# Peripherals_2.net
KiCad netlist of a schematic drawn in Altium Designer
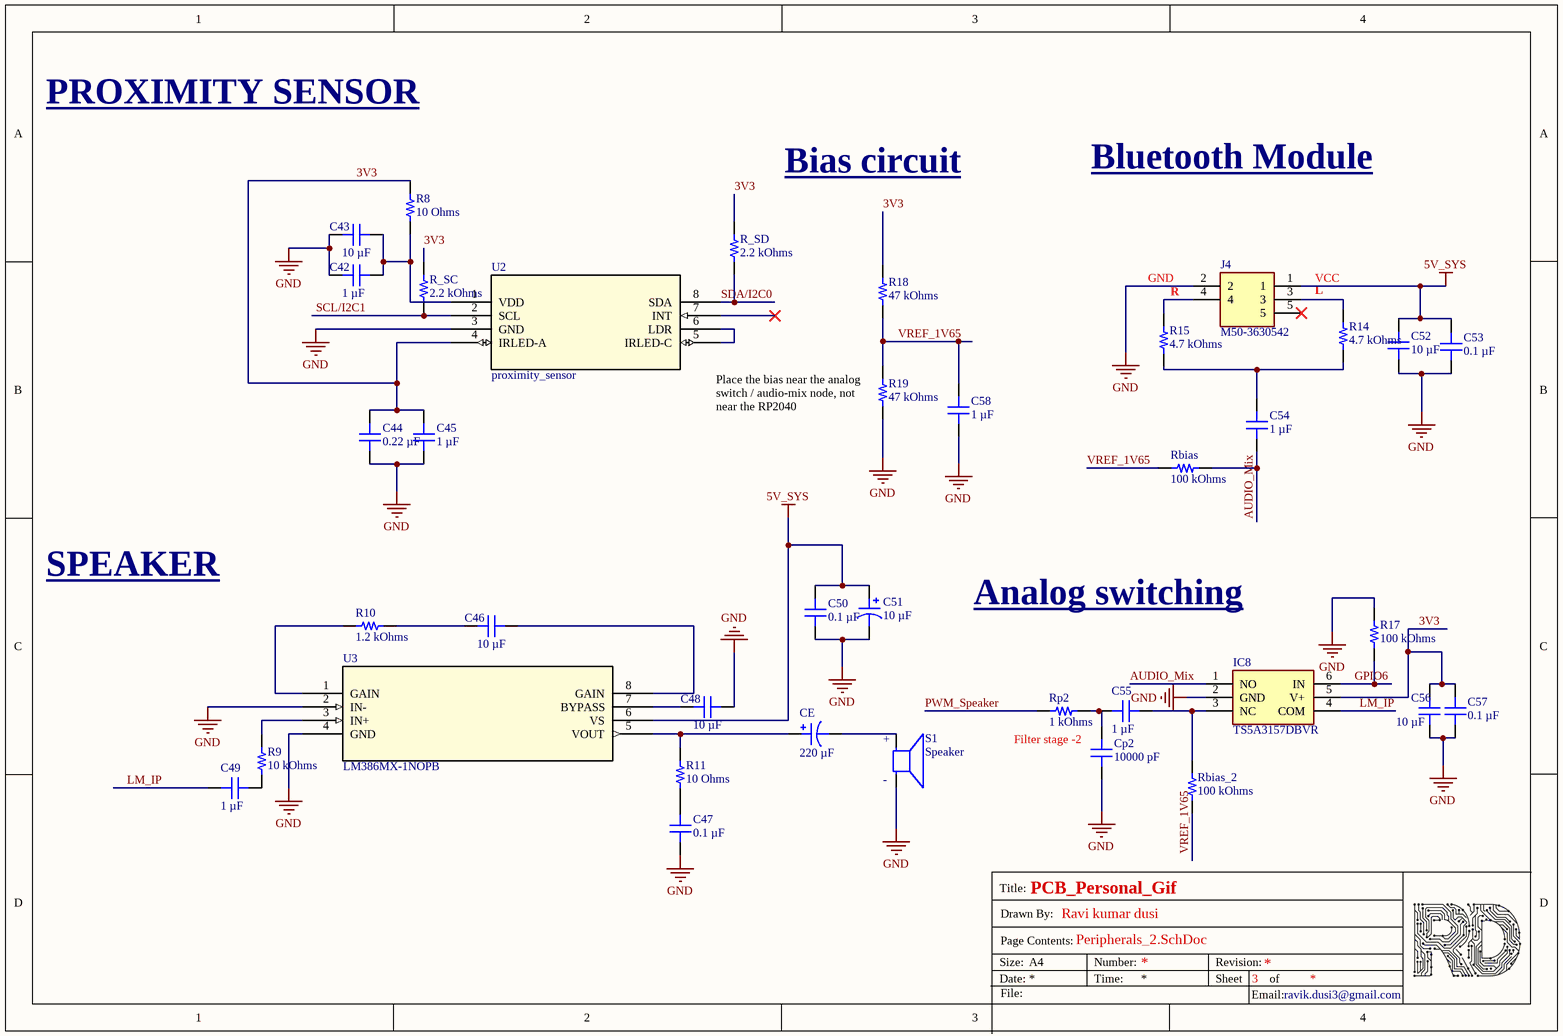
[diagram p0: Peripherals_2.SchDoc]

(export (version "E")
  (design (tool "Eeschema 10.0.6"))
  (components
    (comp (ref "C42")
      (value "1 µF")
      (footprint "CAP 0402_1005")
      (description "CAP CER 1UF 10V X7S 0402")
      (fields
        (field (name "PART NUMBER") "GRM155C71A105KE11D")
        (field (name "MANUFACTURER") "Murata Electronics")
      )
      (libsource (lib "Celestial Altium Library - altium_library") (part "Capacitor"))
    )
    (comp (ref "C43")
      (value "10 µF")
      (footprint "CAP 0402_1005")
      (description "CAP CER 10UF 10V X5R 0402")
      (fields
        (field (name "PART NUMBER") "CL05A106MP8NUB8")
        (field (name "MANUFACTURER") "Samsung Electro-Mechanics")
      )
      (libsource (lib "Celestial Altium Library - altium_library") (part "Capacitor"))
    )
    (comp (ref "C44")
      (value "0.22 µF")
      (footprint "CAP 0402_1005")
      (description "CAP CER 0.22UF 16V X7R 0402")
      (fields
        (field (name "PART NUMBER") "GRM155R71C224KA12D")
        (field (name "MANUFACTURER") "Murata Electronics")
      )
      (libsource (lib "Celestial Altium Library - altium_library") (part "Capacitor"))
    )
    (comp (ref "C45")
      (value "1 µF")
      (footprint "CAP 0402_1005")
      (description "CAP CER 1UF 10V X7S 0402")
      (fields
        (field (name "PART NUMBER") "GRM155C71A105KE11D")
        (field (name "MANUFACTURER") "Murata Electronics")
      )
      (libsource (lib "Celestial Altium Library - altium_library") (part "Capacitor"))
    )
    (comp (ref "C46")
      (value "10 µF")
      (footprint "CAP 0402_1005")
      (description "CAP CER 10UF 10V X5R 0402")
      (fields
        (field (name "PART NUMBER") "CL05A106MP8NUB8")
        (field (name "MANUFACTURER") "Samsung Electro-Mechanics")
      )
      (libsource (lib "Celestial Altium Library - altium_library") (part "Capacitor"))
    )
    (comp (ref "C47")
      (value "0.1 µF")
      (footprint "CAP 0402_1005")
      (description "CAP CER 0402 0.1UF 16V X7R 10%")
      (fields (field (name "PART NUMBER") "C0402C104K4RECAUTO") (field (name "MANUFACTURER") "KEMET"))
      (libsource (lib "Celestial Altium Library - altium_library") (part "Capacitor"))
    )
    (comp (ref "C48")
      (value "10 µF")
      (footprint "CAP 0402_1005")
      (description "CAP CER 10UF 10V X5R 0402")
      (fields
        (field (name "PART NUMBER") "CL05A106MP8NUB8")
        (field (name "MANUFACTURER") "Samsung Electro-Mechanics")
      )
      (libsource (lib "Celestial Altium Library - altium_library") (part "Capacitor"))
    )
    (comp (ref "C49")
      (value "1 µF")
      (footprint "MURATA GRM155 0402_1005")
      (description "CAP CER 1UF 10V X7S 0402")
      (fields
        (field (name "PART NUMBER") "GRM155C71A105KE11D")
        (field (name "CAPACITANCE") "1 µF")
        (field (name "MANUFACTURER") "Murata Electronics")
      )
      (libsource (lib "Celestial Altium Library - altium_library (1)") (part "Capacitor"))
    )
    (comp (ref "C50")
      (value "0.1 µF")
      (footprint "CAP 0402_1005")
      (description "CAP CER 0402 0.1UF 16V X7R 10%")
      (fields (field (name "PART NUMBER") "C0402C104K4RECAUTO") (field (name "MANUFACTURER") "KEMET"))
      (libsource (lib "Celestial Altium Library - altium_library") (part "Capacitor"))
    )
    (comp (ref "C51")
      (value "10 µF")
      (footprint "CAP ALSMD 4.3MM H5.4MM")
      (description "CAP ALUM 10UF 20% 16V SMD")
      (fields (field (name "PART NUMBER") "UWX1C100MCL1GB") (field (name "MANUFACTURER") "Nichicon"))
      (libsource (lib "Celestial Altium Library - altium_library") (part "Polarised Capacitor"))
    )
    (comp (ref "C52")
      (value "10 µF")
      (footprint "CAP 0402_1005")
      (description "CAP CER 10UF 10V X5R 0402")
      (fields
        (field (name "PART NUMBER") "CL05A106MP8NUB8")
        (field (name "CAPACITANCE") "10 µF")
        (field (name "MANUFACTURER") "Samsung Electro-Mechanics")
      )
      (libsource (lib "Celestial Altium Library - altium_library (1)") (part "Capacitor"))
    )
    (comp (ref "C53")
      (value "0.1 µF")
      (footprint "CAP 0402_1005")
      (description "CAP CER 0402 0.1UF 16V X7R 10%")
      (fields
        (field (name "PART NUMBER") "C0402C104K4RECAUTO")
        (field (name "CAPACITANCE") "0.1 µF")
        (field (name "MANUFACTURER") "KEMET")
      )
      (libsource (lib "Celestial Altium Library - altium_library (1)") (part "Capacitor"))
    )
    (comp (ref "C54")
      (value "1 µF")
      (footprint "MURATA GRM155 0402_1005")
      (description "CAP CER 1UF 10V X7S 0402")
      (fields
        (field (name "PART NUMBER") "GRM155C71A105KE11D")
        (field (name "CAPACITANCE") "1 µF")
        (field (name "MANUFACTURER") "Murata Electronics")
      )
      (libsource (lib "Celestial Altium Library - altium_library (1)") (part "Capacitor"))
    )
    (comp (ref "C55")
      (value "1 µF")
      (footprint "MURATA GRM155 0402_1005")
      (description "CAP CER 1UF 10V X7S 0402")
      (fields
        (field (name "PART NUMBER") "GRM155C71A105KE11D")
        (field (name "CAPACITANCE") "1 µF")
        (field (name "MANUFACTURER") "Murata Electronics")
      )
      (libsource (lib "Celestial Altium Library - altium_library (1)") (part "Capacitor"))
    )
    (comp (ref "C56")
      (value "10 µF")
      (footprint "CAP 0402_1005")
      (description "CAP CER 10UF 10V X5R 0402")
      (fields
        (field (name "PART NUMBER") "CL05A106MP8NUB8")
        (field (name "CAPACITANCE") "10 µF")
        (field (name "MANUFACTURER") "Samsung Electro-Mechanics")
      )
      (libsource (lib "Celestial Altium Library - altium_library (1)") (part "Capacitor"))
    )
    (comp (ref "C57")
      (value "0.1 µF")
      (footprint "CAP 0402_1005")
      (description "CAP CER 0402 0.1UF 16V X7R 10%")
      (fields
        (field (name "PART NUMBER") "C0402C104K4RECAUTO")
        (field (name "CAPACITANCE") "0.1 µF")
        (field (name "MANUFACTURER") "KEMET")
      )
      (libsource (lib "Celestial Altium Library - altium_library (1)") (part "Capacitor"))
    )
    (comp (ref "C58")
      (value "1 µF")
      (footprint "MURATA GRM155 0402_1005")
      (description "CAP CER 1UF 10V X7S 0402")
      (fields
        (field (name "PART NUMBER") "GRM155C71A105KE11D")
        (field (name "CAPACITANCE") "1 µF")
        (field (name "MANUFACTURER") "Murata Electronics")
      )
      (libsource (lib "Celestial Altium Library - altium_library (1)") (part "Capacitor"))
    )
    (comp (ref "CE")
      (value "220 µF")
      (footprint "CAP ALSMD 8.3MM H10.5MM")
      (description "CAP ALUM 220UF 20% 35V SMD")
      (fields
        (field (name "PART NUMBER") "EEE-FK1V221P")
        (field (name "MANUFACTURER") "Panasonic Electronic Components")
      )
      (libsource (lib "Celestial Altium Library - altium_library (1)") (part "Polarised Capacitor"))
    )
    (comp (ref "Cp2")
      (value "10000 pF")
      (footprint "CAP 0402_1005")
      (description "CAP CER 0402 10NF 50V X7R 20%")
      (fields
        (field (name "PART NUMBER") "C0402C103M5RECAUTO")
        (field (name "CAPACITANCE") "10000 pF")
        (field (name "MANUFACTURER") "KEMET")
      )
      (libsource (lib "Celestial Altium Library - altium_library (1)") (part "Capacitor"))
    )
    (comp (ref "IC8")
      (value "TS5A3157DBVR")
      (footprint "SamacSys:SOT95P280X145-6N")
      (description "Integrated Circuit")
      (fields (field (name "MOUSER PART NUMBER") "595-TS5A3157DBVR"))
      (libsource (lib "*") (part "TS5A3157DBVR"))
    )
    (comp (ref "J4")
      (value "M50-3630542")
      (footprint "SamacSys:M503630542")
      (description "Connector")
      (fields (field (name "MOUSER PART NUMBER") "855-M50-3630542"))
      (libsource (lib "*") (part "M50-3630542"))
    )
    (comp (ref "R8")
      (value "10 Ohms")
      (footprint "RES 0402_1005")
      (description "RES SMD 10 OHM 0.5% 1/16W 0402")
      (fields
        (field (name "PART NUMBER") "ERA-2AKD100X")
        (field (name "MANUFACTURER") "Panasonic Electronic Components")
      )
      (libsource (lib "Celestial Altium Library - altium_library") (part "Resistor"))
    )
    (comp (ref "R9")
      (value "10 kOhms")
      (footprint "RES 0402_1005")
      (description "RES SMD 10K OHM 5% 1/16W 0402")
      (fields (field (name "PART NUMBER") "AC0402JR-0710KL") (field (name "MANUFACTURER") "Yageo"))
      (libsource (lib "Celestial Altium Library - altium_library") (part "Resistor"))
    )
    (comp (ref "R10")
      (value "1.2 kOhms")
      (footprint "RES 0402_1005")
      (description "RES SMD 1.2K OHM 0.5% 1/16W 0402")
      (fields (field (name "PART NUMBER") "RR0510P-122-D") (field (name "MANUFACTURER") "Susumu"))
      (libsource (lib "Celestial Altium Library - altium_library") (part "Resistor"))
    )
    (comp (ref "R11")
      (value "10 Ohms")
      (footprint "RES 0402_1005")
      (description "RES SMD 10 OHM 0.5% 1/16W 0402")
      (fields
        (field (name "PART NUMBER") "ERA-2AKD100X")
        (field (name "MANUFACTURER") "Panasonic Electronic Components")
      )
      (libsource (lib "Celestial Altium Library - altium_library") (part "Resistor"))
    )
    (comp (ref "R14")
      (value "4.7 kOhms")
      (footprint "YAGEO RES 0402_1005")
      (description "RES SMD 4.7K OHM 1% 1/16W 0402")
      (fields (field (name "PART NUMBER") "RT0402FRE074K7L") (field (name "MANUFACTURER") "Yageo"))
      (libsource (lib "Celestial Altium Library - altium_library (1)") (part "Resistor"))
    )
    (comp (ref "R15")
      (value "4.7 kOhms")
      (footprint "YAGEO RES 0402_1005")
      (description "RES SMD 4.7K OHM 1% 1/16W 0402")
      (fields (field (name "PART NUMBER") "RT0402FRE074K7L") (field (name "MANUFACTURER") "Yageo"))
      (libsource (lib "Celestial Altium Library - altium_library (1)") (part "Resistor"))
    )
    (comp (ref "R17")
      (value "100 kOhms")
      (footprint "RES 0402_1005")
      (description "RES 100K OHM 0.1% 1/10W 0402")
      (fields
        (field (name "PART NUMBER") "RP73PF1E100KBTD")
        (field (name "MANUFACTURER") "TE Connectivity Passive Product")
      )
      (libsource (lib "Celestial Altium Library - altium_library (1)") (part "Resistor"))
    )
    (comp (ref "R18")
      (value "47 kOhms")
      (footprint "YAGEO RES 0402_1005")
      (description "RES SMD 47K OHM 5% 1/16W 0402")
      (fields (field (name "PART NUMBER") "AC0402JR-0747KL") (field (name "MANUFACTURER") "Yageo"))
      (libsource (lib "Celestial Altium Library - altium_library (1)") (part "Resistor"))
    )
    (comp (ref "R19")
      (value "47 kOhms")
      (footprint "YAGEO RES 0402_1005")
      (description "RES SMD 47K OHM 5% 1/16W 0402")
      (fields (field (name "PART NUMBER") "AC0402JR-0747KL") (field (name "MANUFACTURER") "Yageo"))
      (libsource (lib "Celestial Altium Library - altium_library (1)") (part "Resistor"))
    )
    (comp (ref "Rbias")
      (value "100 kOhms")
      (footprint "RES 0402_1005")
      (description "RES 100K OHM 0.1% 1/10W 0402")
      (fields
        (field (name "PART NUMBER") "RP73PF1E100KBTD")
        (field (name "MANUFACTURER") "TE Connectivity Passive Product")
      )
      (libsource (lib "Celestial Altium Library - altium_library (1)") (part "Resistor"))
    )
    (comp (ref "Rbias_2")
      (value "100 kOhms")
      (footprint "RES 0402_1005")
      (description "RES 100K OHM 0.1% 1/10W 0402")
      (fields
        (field (name "PART NUMBER") "RP73PF1E100KBTD")
        (field (name "MANUFACTURER") "TE Connectivity Passive Product")
      )
      (libsource (lib "Celestial Altium Library - altium_library (1)") (part "Resistor"))
    )
    (comp (ref "Rp2")
      (value "1 kOhms")
      (footprint "YAGEO RES 0402_1005")
      (description "RES SMD 1K OHM 0.1% 1/16W 0402")
      (fields (field (name "PART NUMBER") "AT0402BRD071KL") (field (name "MANUFACTURER") "Yageo"))
      (libsource (lib "Celestial Altium Library - altium_library (1)") (part "Resistor"))
    )
    (comp (ref "R_SC")
      (value "2.2 kOhms")
      (footprint "RES 0402_1005")
      (description "RES 2.2K OHM 0.1% 1/16W 0402")
      (fields (field (name "PART NUMBER") "TNPW04022K20BYEP") (field (name "MANUFACTURER") "Vishay Dale"))
      (libsource (lib "Celestial Altium Library - altium_library (1)") (part "Resistor"))
    )
    (comp (ref "R_SD")
      (value "2.2 kOhms")
      (footprint "RES 0402_1005")
      (description "RES 2.2K OHM 0.1% 1/16W 0402")
      (fields (field (name "PART NUMBER") "TNPW04022K20BYEP") (field (name "MANUFACTURER") "Vishay Dale"))
      (libsource (lib "Celestial Altium Library - altium_library (1)") (part "Resistor"))
    )
    (comp (ref "S1")
      (value "Speaker")
      (footprint "SPKR_AS01508MS-SC11-WP-R")
      (description "AS01508MS-SC11-WP-R speaker,0.7 INPUT PWR, 60-20K dB frequency.")
      (libsource (lib "Personal_proj_lib") (part "Speaker"))
    )
    (comp (ref "U2")
      (value "proximity_sensor")
      (footprint "SMT_X01-GS08_VIS")
      (description "Proximity Sensors INTEGRATED PROXIMITY + IR LED.")
      (libsource (lib "Personal_proj_lib") (part "proximity_sensor"))
    )
    (comp (ref "U3")
      (value "LM386MX-1NOPB")
      (footprint "M08A_TEX")
      (description "IC AMP CLASS AB MONO 325MW 8SOIC.AUDIO AMPLIFIER")
      (libsource (lib "LM386MX-1NOPB") (part "LM386MX-1NOPB"))
    )
  )
  (nets
    (net (code "1") (name "/3V3") (class "Default")
      (node (ref "C44") (pin "2") (pinfunction "2_2") (pintype "passive"))
      (node (ref "C45") (pin "1") (pinfunction "1_1") (pintype "passive"))
      (node (ref "C56") (pin "2") (pinfunction "2_2") (pintype "passive"))
      (node (ref "C57") (pin "2") (pinfunction "2_2") (pintype "passive"))
      (node (ref "IC8") (pin "5") (pinfunction "V+_5") (pintype "passive"))
      (node (ref "R18") (pin "2") (pinfunction "2_2") (pintype "passive"))
      (node (ref "R8") (pin "2") (pinfunction "2_2") (pintype "passive"))
      (node (ref "R_SC") (pin "2") (pinfunction "2_2") (pintype "passive"))
      (node (ref "R_SD") (pin "2") (pinfunction "2_2") (pintype "passive"))
      (node (ref "U2") (pin "4") (pinfunction "IRLED-A_4") (pintype "bidirectional"))
    )
    (net (code "2") (name "/AUDIO_Mix") (class "Default")
      (node (ref "C54") (pin "1") (pinfunction "1_1") (pintype "passive"))
      (node (ref "IC8") (pin "1") (pinfunction "NO_1") (pintype "passive"))
      (node (ref "Rbias") (pin "2") (pinfunction "2_2") (pintype "passive"))
    )
    (net (code "3") (name "/GPIO6") (class "Default")
      (node (ref "IC8") (pin "6") (pinfunction "IN_6") (pintype "passive"))
      (node (ref "R17") (pin "1") (pinfunction "1_1") (pintype "passive"))
    )
    (net (code "4") (name "/LM_IP") (class "Default")
      (node (ref "C49") (pin "1") (pinfunction "1_1") (pintype "passive"))
      (node (ref "IC8") (pin "4") (pinfunction "COM_4") (pintype "passive"))
    )
    (net (code "5") (name "/PWM_Speaker") (class "Default")
      (node (ref "Rp2") (pin "1") (pinfunction "1_1") (pintype "passive"))
    )
    (net (code "6") (name "/SCL{slash}I2C1") (class "Default")
      (node (ref "R_SC") (pin "1") (pinfunction "1_1") (pintype "passive"))
      (node (ref "U2") (pin "2") (pinfunction "SCL_2") (pintype "passive"))
    )
    (net (code "7") (name "/SDA{slash}I2C0") (class "Default")
      (node (ref "R_SD") (pin "1") (pinfunction "1_1") (pintype "passive"))
      (node (ref "U2") (pin "8") (pinfunction "SDA_8") (pintype "passive"))
    )
    (net (code "8") (name "/VREF_1V65") (class "Default")
      (node (ref "C58") (pin "2") (pinfunction "2_2") (pintype "passive"))
      (node (ref "R18") (pin "1") (pinfunction "1_1") (pintype "passive"))
      (node (ref "R19") (pin "2") (pinfunction "2_2") (pintype "passive"))
      (node (ref "Rbias") (pin "1") (pinfunction "1_1") (pintype "passive"))
      (node (ref "Rbias_2") (pin "1") (pinfunction "1_1") (pintype "passive"))
    )
    (net (code "9") (name "5V_SYS") (class "Default")
      (node (ref "C50") (pin "2") (pinfunction "2_2") (pintype "passive"))
      (node (ref "C51") (pin "1") (pinfunction "1_1") (pintype "passive"))
      (node (ref "C52") (pin "2") (pinfunction "2_2") (pintype "passive"))
      (node (ref "C53") (pin "2") (pinfunction "2_2") (pintype "passive"))
      (node (ref "J4") (pin "1") (pinfunction "1_1") (pintype "passive"))
      (node (ref "U3") (pin "6") (pinfunction "VS_6") (pintype "power_in"))
    )
    (net (code "10") (name "GND") (class "Default")
      (node (ref "C42") (pin "2") (pinfunction "2_2") (pintype "passive"))
      (node (ref "C43") (pin "1") (pinfunction "1_1") (pintype "passive"))
      (node (ref "C44") (pin "1") (pinfunction "1_1") (pintype "passive"))
      (node (ref "C45") (pin "2") (pinfunction "2_2") (pintype "passive"))
      (node (ref "C47") (pin "1") (pinfunction "1_1") (pintype "passive"))
      (node (ref "C48") (pin "2") (pinfunction "2_2") (pintype "passive"))
      (node (ref "C50") (pin "1") (pinfunction "1_1") (pintype "passive"))
      (node (ref "C51") (pin "2") (pinfunction "2_2") (pintype "passive"))
      (node (ref "C52") (pin "1") (pinfunction "1_1") (pintype "passive"))
      (node (ref "C53") (pin "1") (pinfunction "1_1") (pintype "passive"))
      (node (ref "C56") (pin "1") (pinfunction "1_1") (pintype "passive"))
      (node (ref "C57") (pin "1") (pinfunction "1_1") (pintype "passive"))
      (node (ref "C58") (pin "1") (pinfunction "1_1") (pintype "passive"))
      (node (ref "Cp2") (pin "1") (pinfunction "1_1") (pintype "passive"))
      (node (ref "IC8") (pin "2") (pinfunction "GND_2") (pintype "passive"))
      (node (ref "J4") (pin "2") (pinfunction "2_2") (pintype "passive"))
      (node (ref "R17") (pin "2") (pinfunction "2_2") (pintype "passive"))
      (node (ref "R19") (pin "1") (pinfunction "1_1") (pintype "passive"))
      (node (ref "S1") (pin "N") (pinfunction "NEG_N") (pintype "passive"))
      (node (ref "U2") (pin "3") (pinfunction "GND_3") (pintype "power_in"))
      (node (ref "U3") (pin "2") (pinfunction "IN-_2") (pintype "input"))
      (node (ref "U3") (pin "4") (pinfunction "GND_4") (pintype "power_in"))
    )
    (net (code "11") (name "Net-(C46-Pad1)") (class "Default")
      (node (ref "C46") (pin "1") (pinfunction "1_1") (pintype "passive"))
      (node (ref "R10") (pin "2") (pinfunction "2_2") (pintype "passive"))
    )
    (net (code "12") (name "Net-(C46-Pad2)") (class "Default")
      (node (ref "C46") (pin "2") (pinfunction "2_2") (pintype "passive"))
      (node (ref "U3") (pin "8") (pinfunction "GAIN_8") (pintype "passive"))
    )
    (net (code "13") (name "Net-(C47-Pad2)") (class "Default")
      (node (ref "C47") (pin "2") (pinfunction "2_2") (pintype "passive"))
      (node (ref "R11") (pin "1") (pinfunction "1_1") (pintype "passive"))
    )
    (net (code "14") (name "Net-(C49-Pad2)") (class "Default")
      (node (ref "C49") (pin "2") (pinfunction "2_2") (pintype "passive"))
      (node (ref "R9") (pin "1") (pinfunction "1_1") (pintype "passive"))
    )
    (net (code "15") (name "Net-(C54-Pad2)") (class "Default")
      (node (ref "C54") (pin "2") (pinfunction "2_2") (pintype "passive"))
      (node (ref "R14") (pin "1") (pinfunction "1_1") (pintype "passive"))
      (node (ref "R15") (pin "1") (pinfunction "1_1") (pintype "passive"))
    )
    (net (code "16") (name "Net-(C55-Pad1)") (class "Default")
      (node (ref "C55") (pin "1") (pinfunction "1_1") (pintype "passive"))
      (node (ref "Cp2") (pin "2") (pinfunction "2_2") (pintype "passive"))
      (node (ref "Rp2") (pin "2") (pinfunction "2_2") (pintype "passive"))
    )
    (net (code "17") (name "Net-(IC8-NC)") (class "Default")
      (node (ref "C55") (pin "2") (pinfunction "2_2") (pintype "passive"))
      (node (ref "IC8") (pin "3") (pinfunction "NC_3") (pintype "passive"))
      (node (ref "Rbias_2") (pin "2") (pinfunction "2_2") (pintype "passive"))
    )
    (net (code "18") (name "Net-(J4-Pad3)") (class "Default")
      (node (ref "J4") (pin "3") (pinfunction "3_3") (pintype "passive"))
      (node (ref "R14") (pin "2") (pinfunction "2_2") (pintype "passive"))
    )
    (net (code "19") (name "Net-(J4-Pad4)") (class "Default")
      (node (ref "J4") (pin "4") (pinfunction "4_4") (pintype "passive"))
      (node (ref "R15") (pin "2") (pinfunction "2_2") (pintype "passive"))
    )
    (net (code "20") (name "Net-(R10-Pad1)") (class "Default")
      (node (ref "R10") (pin "1") (pinfunction "1_1") (pintype "passive"))
      (node (ref "U3") (pin "1") (pinfunction "GAIN_1") (pintype "passive"))
    )
    (net (code "21") (name "Net-(S1-POS)") (class "Default")
      (node (ref "CE") (pin "2") (pinfunction "2_2") (pintype "passive"))
      (node (ref "S1") (pin "P") (pinfunction "POS_P") (pintype "passive"))
    )
    (net (code "22") (name "Net-(U2-IRLED-C)") (class "Default")
      (node (ref "U2") (pin "5") (pinfunction "IRLED-C_5") (pintype "bidirectional"))
      (node (ref "U2") (pin "6") (pinfunction "LDR_6") (pintype "passive"))
    )
    (net (code "23") (name "Net-(U2-VDD)") (class "Default")
      (node (ref "C42") (pin "1") (pinfunction "1_1") (pintype "passive"))
      (node (ref "C43") (pin "2") (pinfunction "2_2") (pintype "passive"))
      (node (ref "R8") (pin "1") (pinfunction "1_1") (pintype "passive"))
      (node (ref "U2") (pin "1") (pinfunction "VDD_1") (pintype "power_in"))
    )
    (net (code "24") (name "Net-(U3-BYPASS)") (class "Default")
      (node (ref "C48") (pin "1") (pinfunction "1_1") (pintype "passive"))
      (node (ref "U3") (pin "7") (pinfunction "BYPASS_7") (pintype "passive"))
    )
    (net (code "25") (name "Net-(U3-IN+)") (class "Default")
      (node (ref "R9") (pin "2") (pinfunction "2_2") (pintype "passive"))
      (node (ref "U3") (pin "3") (pinfunction "IN+_3") (pintype "input"))
    )
    (net (code "26") (name "Net-(U3-VOUT)") (class "Default")
      (node (ref "CE") (pin "1") (pinfunction "1_1") (pintype "passive"))
      (node (ref "R11") (pin "2") (pinfunction "2_2") (pintype "passive"))
      (node (ref "U3") (pin "5") (pinfunction "VOUT_5") (pintype "output"))
    )
    (net (code "27") (name "unconnected-(J4-Pad5)") (class "Default")
      (node (ref "J4") (pin "5") (pinfunction "5_5") (pintype "passive+no_connect"))
    )
    (net (code "28") (name "unconnected-(U2-INT-Pad7)") (class "Default")
      (node (ref "U2") (pin "7") (pinfunction "INT_7") (pintype "input+no_connect"))
    )
  )
)
